# VisualightMicroDIY_035_gnd.net
KiCad netlist of a schematic drawn in EAGLE
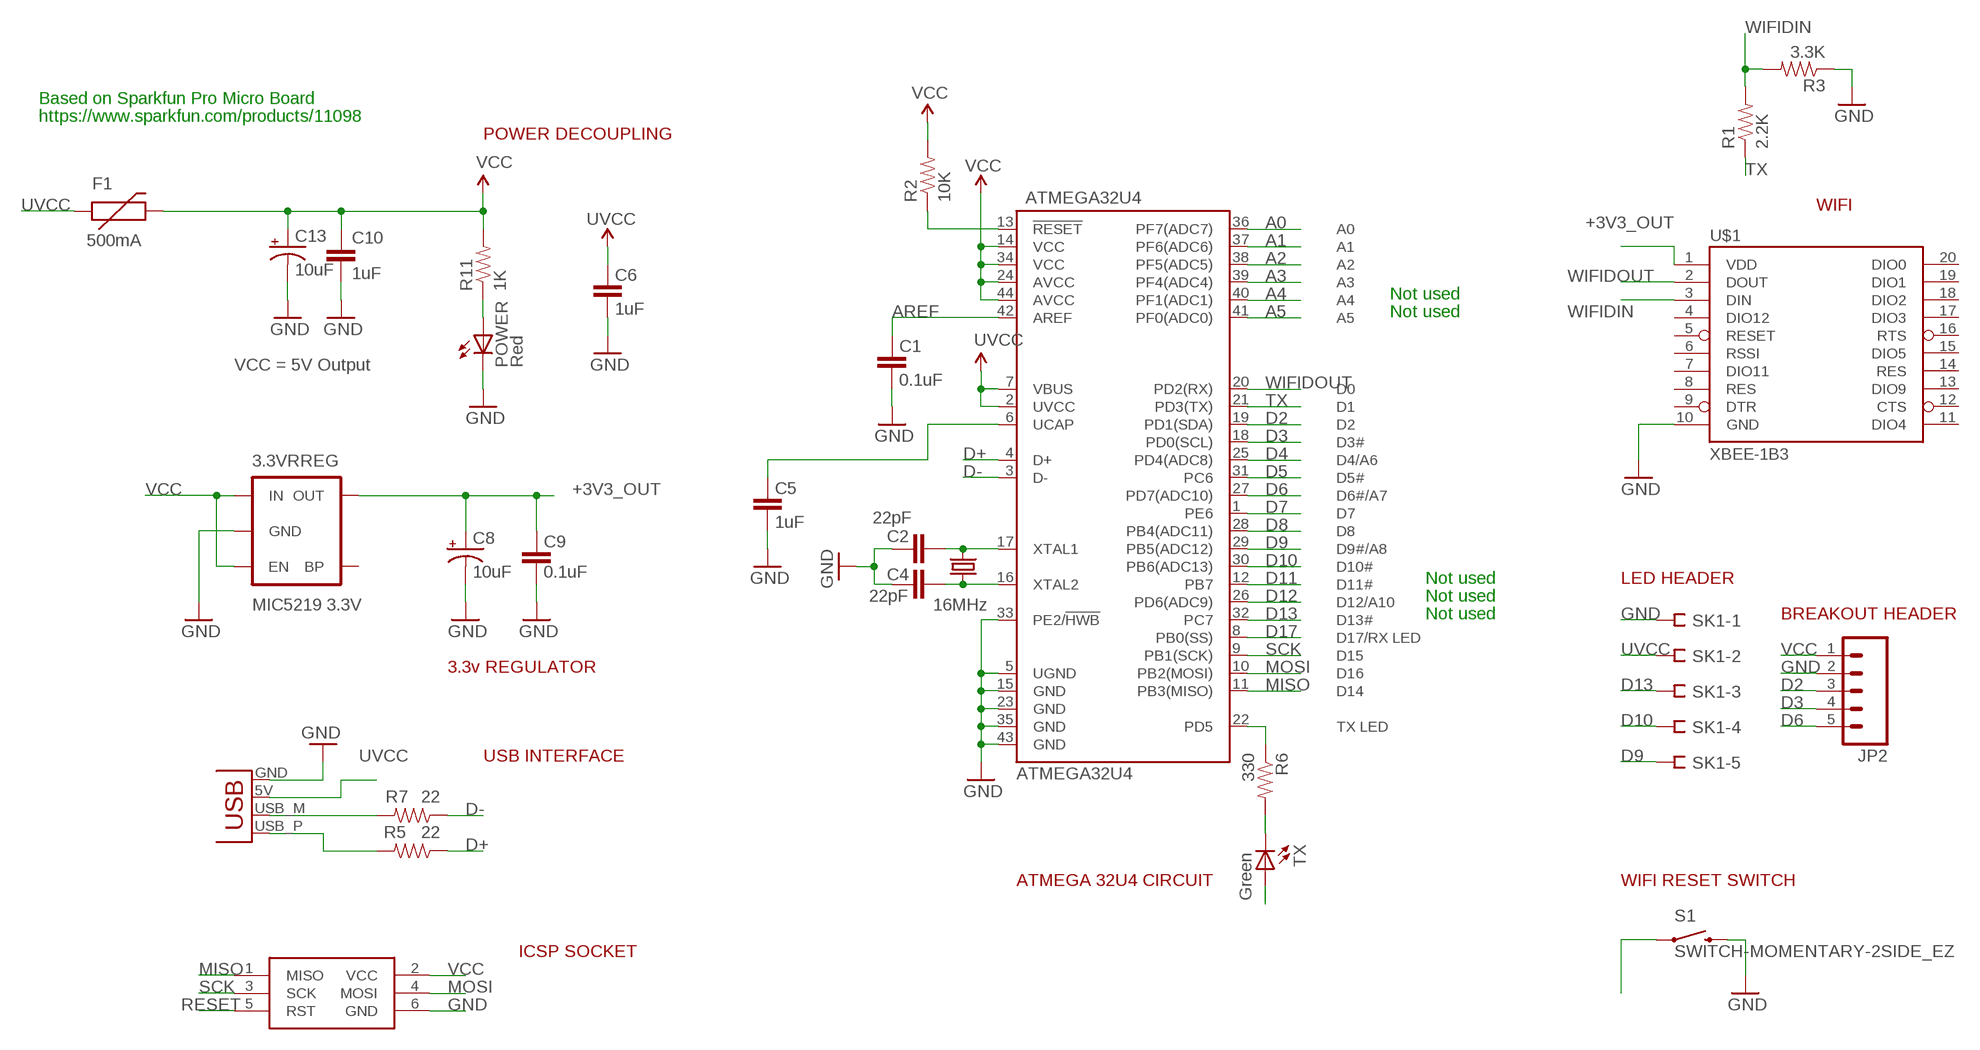
[diagram p0: schematic, sheet 1]

(export (version "E")
  (design (tool "Eeschema 10.0.6"))
  (components
    (comp (ref "3.3VRREG")
      (value "MIC5219 3.3V")
      (footprint "eagle-import:SOT23-5")
      (libsource (lib "eagle-import") (part "V_REG_MIC52193.3V"))
    )
    (comp (ref "ATMEGA32U4")
      (value "ATMEGA32U4")
      (footprint "eagle-import:SPARKFUN-DIGITALIC_TQFP44")
      (libsource (lib "eagle-import") (part "ATMEGA32U4TQFP"))
    )
    (comp (ref "C1")
      (value "0.1uF")
      (footprint "eagle-import:0402-CAP")
      (libsource (lib "eagle-import") (part "CAP0402-CAP"))
    )
    (comp (ref "C2")
      (value "22pF")
      (footprint "eagle-import:0402-CAP")
      (libsource (lib "eagle-import") (part "CAP0402-CAP"))
    )
    (comp (ref "C4")
      (value "22pF")
      (footprint "eagle-import:0402-CAP")
      (libsource (lib "eagle-import") (part "CAP0402-CAP"))
    )
    (comp (ref "C5")
      (value "1uF")
      (footprint "eagle-import:0402-CAP")
      (libsource (lib "eagle-import") (part "CAP0402-CAP"))
    )
    (comp (ref "C6")
      (value "1uF")
      (footprint "eagle-import:0402-CAP")
      (libsource (lib "eagle-import") (part "CAP0402-CAP"))
    )
    (comp (ref "C8")
      (value "10uF")
      (footprint "eagle-import:EIA3216")
      (libsource (lib "eagle-import") (part "CAP_POL1206"))
    )
    (comp (ref "C9")
      (value "0.1uF")
      (footprint "eagle-import:0402-CAP")
      (libsource (lib "eagle-import") (part "CAP0402-CAP"))
    )
    (comp (ref "C10")
      (value "1uF")
      (footprint "eagle-import:0402-CAP")
      (libsource (lib "eagle-import") (part "CAP0402-CAP"))
    )
    (comp (ref "C13")
      (value "10uF")
      (footprint "eagle-import:EIA3216")
      (libsource (lib "eagle-import") (part "CAP_POL1206"))
    )
    (comp (ref "F1")
      (value "500mA")
      (footprint "eagle-import:PTC-1206")
      (libsource (lib "eagle-import") (part "PTCSMD"))
    )
    (comp (ref "ISP1")
      (value "AVRISP-6")
      (footprint "eagle-import:AVRISP")
      (libsource (lib "eagle-import") (part "AVRISP-6"))
    )
    (comp (ref "JP2")
      (value "M05PTH")
      (footprint "eagle-import:1X05")
      (libsource (lib "eagle-import") (part "M05PTH"))
    )
    (comp (ref "POWER")
      (value "Red")
      (footprint "eagle-import:LED-0603")
      (libsource (lib "eagle-import") (part "LED0603"))
    )
    (comp (ref "R1")
      (value "2.2K")
      (footprint "eagle-import:0402-RES")
      (libsource (lib "eagle-import") (part "RESISTOR0402-RES"))
    )
    (comp (ref "R2")
      (value "10K")
      (footprint "eagle-import:0402-RES")
      (libsource (lib "eagle-import") (part "RESISTOR0402-RES"))
    )
    (comp (ref "R3")
      (value "3.3K")
      (footprint "eagle-import:0402-RES")
      (libsource (lib "eagle-import") (part "RESISTOR0402-RES"))
    )
    (comp (ref "R5")
      (value "22")
      (footprint "eagle-import:0402-RES")
      (libsource (lib "eagle-import") (part "RESISTOR0402-RES"))
    )
    (comp (ref "R6")
      (value "330")
      (footprint "eagle-import:0402-RES")
      (libsource (lib "eagle-import") (part "RESISTOR0402-RES"))
    )
    (comp (ref "R7")
      (value "22")
      (footprint "eagle-import:0402-RES")
      (libsource (lib "eagle-import") (part "RESISTOR0402-RES"))
    )
    (comp (ref "R11")
      (value "1K")
      (footprint "eagle-import:0402-RES")
      (libsource (lib "eagle-import") (part "RESISTOR0402-RES"))
    )
    (comp (ref "S1")
      (value "SWITCH-MOMENTARY-2SIDE_EZ")
      (footprint "eagle-import:TACTILE-PTH-SIDEEZ")
      (libsource (lib "eagle-import") (part "SWITCH-MOMENTARY-2SIDE_EZ"))
    )
    (comp (ref "SK1")
      (value "DF3-05S")
      (footprint "eagle-import:DF3S-05")
      (libsource (lib "eagle-import") (part "DF3-05S"))
    )
    (comp (ref "TX")
      (value "Green")
      (footprint "eagle-import:LED-0603")
      (libsource (lib "eagle-import") (part "LED0603"))
    )
    (comp (ref "U$1")
      (value "XBEE-1B3")
      (footprint "eagle-import:XBEE-SMD")
      (libsource (lib "eagle-import") (part "XBEE-1B3"))
    )
    (comp (ref "X2")
      (value "USBPCB")
      (footprint "eagle-import:USB-A-PCB")
      (libsource (lib "eagle-import") (part "USBPCB"))
    )
    (comp (ref "Y1")
      (value "16MHz")
      (footprint "eagle-import:CRYSTAL-SMD-5X3")
      (libsource (lib "eagle-import") (part "CRYSTAL5X3"))
    )
  )
  (nets
    (net (code "1") (name "/+3V3_OUT") (class "Default")
      (node (ref "3.3VRREG") (pin "5") (pinfunction "OUT_5") (pintype "passive"))
      (node (ref "C8") (pin "A") (pinfunction "+_A") (pintype "passive"))
      (node (ref "C9") (pin "2") (pinfunction "2_2") (pintype "passive"))
      (node (ref "U$1") (pin "1") (pinfunction "VDD_1") (pintype "power_in"))
    )
    (net (code "2") (name "/A0") (class "Default")
      (node (ref "ATMEGA32U4") (pin "36") (pinfunction "PF7(ADC7)_36") (pintype "bidirectional"))
    )
    (net (code "3") (name "/A1") (class "Default")
      (node (ref "ATMEGA32U4") (pin "37") (pinfunction "PF6(ADC6)_37") (pintype "bidirectional"))
    )
    (net (code "4") (name "/A2") (class "Default")
      (node (ref "ATMEGA32U4") (pin "38") (pinfunction "PF5(ADC5)_38") (pintype "bidirectional"))
    )
    (net (code "5") (name "/A3") (class "Default")
      (node (ref "ATMEGA32U4") (pin "39") (pinfunction "PF4(ADC4)_39") (pintype "bidirectional"))
    )
    (net (code "6") (name "/A4") (class "Default")
      (node (ref "ATMEGA32U4") (pin "40") (pinfunction "PF1(ADC1)_40") (pintype "bidirectional"))
    )
    (net (code "7") (name "/A5") (class "Default")
      (node (ref "ATMEGA32U4") (pin "41") (pinfunction "PF0(ADC0)_41") (pintype "bidirectional"))
    )
    (net (code "8") (name "/AREF") (class "Default")
      (node (ref "ATMEGA32U4") (pin "42") (pinfunction "AREF_42") (pintype "bidirectional"))
      (node (ref "C1") (pin "2") (pinfunction "2_2") (pintype "passive"))
    )
    (net (code "9") (name "/D+") (class "Default")
      (node (ref "ATMEGA32U4") (pin "4") (pinfunction "D+_4") (pintype "bidirectional"))
      (node (ref "R5") (pin "1") (pinfunction "1_1") (pintype "passive"))
    )
    (net (code "10") (name "/D-") (class "Default")
      (node (ref "ATMEGA32U4") (pin "3") (pinfunction "D-_3") (pintype "bidirectional"))
      (node (ref "R7") (pin "1") (pinfunction "1_1") (pintype "passive"))
    )
    (net (code "11") (name "/D2") (class "Default")
      (node (ref "ATMEGA32U4") (pin "19") (pinfunction "PD1(SDA)_19") (pintype "bidirectional"))
      (node (ref "JP2") (pin "3") (pinfunction "3_3") (pintype "passive"))
    )
    (net (code "12") (name "/D3") (class "Default")
      (node (ref "ATMEGA32U4") (pin "18") (pinfunction "PD0(SCL)_18") (pintype "bidirectional"))
      (node (ref "JP2") (pin "4") (pinfunction "4_4") (pintype "passive"))
    )
    (net (code "13") (name "/D4") (class "Default")
      (node (ref "ATMEGA32U4") (pin "25") (pinfunction "PD4(ADC8)_25") (pintype "bidirectional"))
    )
    (net (code "14") (name "/D5") (class "Default")
      (node (ref "ATMEGA32U4") (pin "31") (pinfunction "PC6_31") (pintype "bidirectional"))
    )
    (net (code "15") (name "/D6") (class "Default")
      (node (ref "ATMEGA32U4") (pin "27") (pinfunction "PD7(ADC10)_27") (pintype "bidirectional"))
      (node (ref "JP2") (pin "5") (pinfunction "5_5") (pintype "passive"))
    )
    (net (code "16") (name "/D7") (class "Default")
      (node (ref "ATMEGA32U4") (pin "1") (pinfunction "PE6_1") (pintype "bidirectional"))
      (node (ref "S1") (pin "1") (pinfunction "1_1") (pintype "passive"))
    )
    (net (code "17") (name "/D8") (class "Default")
      (node (ref "ATMEGA32U4") (pin "28") (pinfunction "PB4(ADC11)_28") (pintype "bidirectional"))
    )
    (net (code "18") (name "/D9") (class "Default")
      (node (ref "ATMEGA32U4") (pin "29") (pinfunction "PB5(ADC12)_29") (pintype "bidirectional"))
      (node (ref "SK1") (pin "5") (pinfunction "S_5") (pintype "passive"))
    )
    (net (code "19") (name "/D10") (class "Default")
      (node (ref "ATMEGA32U4") (pin "30") (pinfunction "PB6(ADC13)_30") (pintype "bidirectional"))
      (node (ref "SK1") (pin "4") (pinfunction "S_4") (pintype "passive"))
    )
    (net (code "20") (name "/D11") (class "Default")
      (node (ref "ATMEGA32U4") (pin "12") (pinfunction "PB7_12") (pintype "bidirectional"))
    )
    (net (code "21") (name "/D12") (class "Default")
      (node (ref "ATMEGA32U4") (pin "26") (pinfunction "PD6(ADC9)_26") (pintype "bidirectional"))
    )
    (net (code "22") (name "/D13") (class "Default")
      (node (ref "ATMEGA32U4") (pin "32") (pinfunction "PC7_32") (pintype "bidirectional"))
      (node (ref "SK1") (pin "3") (pinfunction "S_3") (pintype "passive"))
    )
    (net (code "23") (name "/D17") (class "Default")
      (node (ref "ATMEGA32U4") (pin "8") (pinfunction "PB0(SS)_8") (pintype "bidirectional"))
    )
    (net (code "24") (name "/MISO") (class "Default")
      (node (ref "ATMEGA32U4") (pin "11") (pinfunction "PB3(MISO)_11") (pintype "bidirectional"))
      (node (ref "ISP1") (pin "1") (pinfunction "MISO_1") (pintype "input"))
    )
    (net (code "25") (name "/MOSI") (class "Default")
      (node (ref "ATMEGA32U4") (pin "10") (pinfunction "PB2(MOSI)_10") (pintype "bidirectional"))
      (node (ref "ISP1") (pin "4") (pinfunction "MOSI_4") (pintype "output"))
    )
    (net (code "26") (name "/RESET") (class "Default")
      (node (ref "ATMEGA32U4") (pin "13") (pinfunction "~{RESET}_13") (pintype "bidirectional"))
      (node (ref "ISP1") (pin "5") (pinfunction "RST_5") (pintype "output"))
      (node (ref "R2") (pin "1") (pinfunction "1_1") (pintype "passive"))
    )
    (net (code "27") (name "/SCK") (class "Default")
      (node (ref "ATMEGA32U4") (pin "9") (pinfunction "PB1(SCK)_9") (pintype "bidirectional"))
      (node (ref "ISP1") (pin "3") (pinfunction "SCK_3") (pintype "output"))
    )
    (net (code "28") (name "/TX") (class "Default")
      (node (ref "ATMEGA32U4") (pin "21") (pinfunction "PD3(TX)_21") (pintype "bidirectional"))
      (node (ref "R1") (pin "1") (pinfunction "1_1") (pintype "passive"))
    )
    (net (code "29") (name "/WIFIDIN") (class "Default")
      (node (ref "R1") (pin "2") (pinfunction "2_2") (pintype "passive"))
      (node (ref "R3") (pin "2") (pinfunction "2_2") (pintype "passive"))
      (node (ref "U$1") (pin "3") (pinfunction "DIN_3") (pintype "input"))
    )
    (net (code "30") (name "/WIFIDOUT") (class "Default")
      (node (ref "ATMEGA32U4") (pin "20") (pinfunction "PD2(RX)_20") (pintype "bidirectional"))
      (node (ref "U$1") (pin "2") (pinfunction "DOUT_2") (pintype "output"))
    )
    (net (code "31") (name "GND") (class "Default")
      (node (ref "3.3VRREG") (pin "2") (pinfunction "GND_2") (pintype "input"))
      (node (ref "ATMEGA32U4") (pin "15") (pinfunction "GND_15") (pintype "bidirectional"))
      (node (ref "ATMEGA32U4") (pin "23") (pinfunction "GND_23") (pintype "bidirectional"))
      (node (ref "ATMEGA32U4") (pin "33") (pinfunction "PE2/~{HWB}_33") (pintype "bidirectional"))
      (node (ref "ATMEGA32U4") (pin "35") (pinfunction "GND_35") (pintype "bidirectional"))
      (node (ref "ATMEGA32U4") (pin "43") (pinfunction "GND_43") (pintype "bidirectional"))
      (node (ref "ATMEGA32U4") (pin "5") (pinfunction "UGND_5") (pintype "bidirectional"))
      (node (ref "C1") (pin "1") (pinfunction "1_1") (pintype "passive"))
      (node (ref "C10") (pin "2") (pinfunction "2_2") (pintype "passive"))
      (node (ref "C13") (pin "C") (pinfunction "-_C") (pintype "passive"))
      (node (ref "C2") (pin "2") (pinfunction "2_2") (pintype "passive"))
      (node (ref "C4") (pin "2") (pinfunction "2_2") (pintype "passive"))
      (node (ref "C5") (pin "1") (pinfunction "1_1") (pintype "passive"))
      (node (ref "C6") (pin "1") (pinfunction "1_1") (pintype "passive"))
      (node (ref "C8") (pin "C") (pinfunction "-_C") (pintype "passive"))
      (node (ref "C9") (pin "1") (pinfunction "1_1") (pintype "passive"))
      (node (ref "ISP1") (pin "6") (pinfunction "GND_6") (pintype "power_in"))
      (node (ref "JP2") (pin "2") (pinfunction "2_2") (pintype "passive"))
      (node (ref "POWER") (pin "C") (pinfunction "C_C") (pintype "passive"))
      (node (ref "R3") (pin "1") (pinfunction "1_1") (pintype "passive"))
      (node (ref "S1") (pin "2") (pinfunction "2_2") (pintype "passive"))
      (node (ref "SK1") (pin "1") (pinfunction "S_1") (pintype "passive"))
      (node (ref "U$1") (pin "10") (pinfunction "GND_10") (pintype "power_in"))
      (node (ref "X2") (pin "GND") (pinfunction "GND_GND") (pintype "bidirectional"))
    )
    (net (code "32") (name "Net-(ATMEGA32U4-PD5)") (class "Default")
      (node (ref "ATMEGA32U4") (pin "22") (pinfunction "PD5_22") (pintype "bidirectional"))
      (node (ref "R6") (pin "1") (pinfunction "1_1") (pintype "passive"))
    )
    (net (code "33") (name "Net-(ATMEGA32U4-UCAP)") (class "Default")
      (node (ref "ATMEGA32U4") (pin "6") (pinfunction "UCAP_6") (pintype "bidirectional"))
      (node (ref "C5") (pin "2") (pinfunction "2_2") (pintype "passive"))
    )
    (net (code "34") (name "Net-(ATMEGA32U4-XTAL1)") (class "Default")
      (node (ref "ATMEGA32U4") (pin "17") (pinfunction "XTAL1_17") (pintype "bidirectional"))
      (node (ref "C2") (pin "1") (pinfunction "1_1") (pintype "passive"))
      (node (ref "Y1") (pin "3") (pinfunction "2_3") (pintype "passive"))
    )
    (net (code "35") (name "Net-(ATMEGA32U4-XTAL2)") (class "Default")
      (node (ref "ATMEGA32U4") (pin "16") (pinfunction "XTAL2_16") (pintype "bidirectional"))
      (node (ref "C4") (pin "1") (pinfunction "1_1") (pintype "passive"))
      (node (ref "Y1") (pin "1") (pinfunction "1_1") (pintype "passive"))
    )
    (net (code "36") (name "Net-(POWER-PadA)") (class "Default")
      (node (ref "POWER") (pin "A") (pinfunction "A_A") (pintype "passive"))
      (node (ref "R11") (pin "1") (pinfunction "1_1") (pintype "passive"))
    )
    (net (code "37") (name "Net-(R6-Pad2)") (class "Default")
      (node (ref "R6") (pin "2") (pinfunction "2_2") (pintype "passive"))
      (node (ref "TX") (pin "C") (pinfunction "C_C") (pintype "passive"))
    )
    (net (code "38") (name "Net-(X2-D+)") (class "Default")
      (node (ref "R5") (pin "2") (pinfunction "2_2") (pintype "passive"))
      (node (ref "X2") (pin "USB_P") (pinfunction "D+_USB_P") (pintype "bidirectional"))
    )
    (net (code "39") (name "Net-(X2-D-)") (class "Default")
      (node (ref "R7") (pin "2") (pinfunction "2_2") (pintype "passive"))
      (node (ref "X2") (pin "USB_M") (pinfunction "D-_USB_M") (pintype "bidirectional"))
    )
    (net (code "40") (name "UVCC") (class "Default")
      (node (ref "ATMEGA32U4") (pin "2") (pinfunction "UVCC_2") (pintype "bidirectional"))
      (node (ref "ATMEGA32U4") (pin "7") (pinfunction "VBUS_7") (pintype "bidirectional"))
      (node (ref "C6") (pin "2") (pinfunction "2_2") (pintype "passive"))
      (node (ref "F1") (pin "1") (pinfunction "1_1") (pintype "bidirectional"))
      (node (ref "SK1") (pin "2") (pinfunction "S_2") (pintype "passive"))
      (node (ref "X2") (pin "5V") (pinfunction "VBUS_5V") (pintype "bidirectional"))
    )
    (net (code "41") (name "VCC") (class "Default")
      (node (ref "3.3VRREG") (pin "1") (pinfunction "IN_1") (pintype "input"))
      (node (ref "3.3VRREG") (pin "3") (pinfunction "EN_3") (pintype "input"))
      (node (ref "ATMEGA32U4") (pin "14") (pinfunction "VCC_14") (pintype "bidirectional"))
      (node (ref "ATMEGA32U4") (pin "24") (pinfunction "AVCC_24") (pintype "bidirectional"))
      (node (ref "ATMEGA32U4") (pin "34") (pinfunction "VCC_34") (pintype "bidirectional"))
      (node (ref "ATMEGA32U4") (pin "44") (pinfunction "AVCC_44") (pintype "bidirectional"))
      (node (ref "C10") (pin "1") (pinfunction "1_1") (pintype "passive"))
      (node (ref "C13") (pin "A") (pinfunction "+_A") (pintype "passive"))
      (node (ref "F1") (pin "2") (pinfunction "2_2") (pintype "bidirectional"))
      (node (ref "ISP1") (pin "2") (pinfunction "VCC_2") (pintype "power_in"))
      (node (ref "JP2") (pin "1") (pinfunction "1_1") (pintype "passive"))
      (node (ref "R11") (pin "2") (pinfunction "2_2") (pintype "passive"))
      (node (ref "R2") (pin "2") (pinfunction "2_2") (pintype "passive"))
      (node (ref "TX") (pin "A") (pinfunction "A_A") (pintype "passive"))
    )
    (net (code "42") (name "unconnected-(3.3VRREG-BP-Pad4)") (class "Default")
      (node (ref "3.3VRREG") (pin "4") (pinfunction "BP_4") (pintype "input"))
    )
    (net (code "43") (name "unconnected-(U$1-CTS-Pad12)") (class "Default")
      (node (ref "U$1") (pin "12") (pinfunction "CTS_12") (pintype "output"))
    )
    (net (code "44") (name "unconnected-(U$1-DIO0-Pad20)") (class "Default")
      (node (ref "U$1") (pin "20") (pinfunction "DIO0_20") (pintype "bidirectional"))
    )
    (net (code "45") (name "unconnected-(U$1-DIO1-Pad19)") (class "Default")
      (node (ref "U$1") (pin "19") (pinfunction "DIO1_19") (pintype "bidirectional"))
    )
    (net (code "46") (name "unconnected-(U$1-DIO2-Pad18)") (class "Default")
      (node (ref "U$1") (pin "18") (pinfunction "DIO2_18") (pintype "bidirectional"))
    )
    (net (code "47") (name "unconnected-(U$1-DIO3-Pad17)") (class "Default")
      (node (ref "U$1") (pin "17") (pinfunction "DIO3_17") (pintype "bidirectional"))
    )
    (net (code "48") (name "unconnected-(U$1-DIO4-Pad11)") (class "Default")
      (node (ref "U$1") (pin "11") (pinfunction "DIO4_11") (pintype "bidirectional"))
    )
    (net (code "49") (name "unconnected-(U$1-DIO5-Pad15)") (class "Default")
      (node (ref "U$1") (pin "15") (pinfunction "DIO5_15") (pintype "bidirectional"))
    )
    (net (code "50") (name "unconnected-(U$1-DIO9-Pad13)") (class "Default")
      (node (ref "U$1") (pin "13") (pinfunction "DIO9_13") (pintype "bidirectional"))
    )
    (net (code "51") (name "unconnected-(U$1-DIO11-Pad7)") (class "Default")
      (node (ref "U$1") (pin "7") (pinfunction "DIO11_7") (pintype "bidirectional"))
    )
    (net (code "52") (name "unconnected-(U$1-DIO12-Pad4)") (class "Default")
      (node (ref "U$1") (pin "4") (pinfunction "DIO12_4") (pintype "bidirectional"))
    )
    (net (code "53") (name "unconnected-(U$1-DTR-Pad9)") (class "Default")
      (node (ref "U$1") (pin "9") (pinfunction "DTR_9") (pintype "bidirectional"))
    )
    (net (code "54") (name "unconnected-(U$1-RES-Pad8)") (class "Default")
      (node (ref "U$1") (pin "8") (pinfunction "RES_8") (pintype "bidirectional"))
    )
    (net (code "55") (name "unconnected-(U$1-RES-Pad14)") (class "Default")
      (node (ref "U$1") (pin "14") (pinfunction "RES_14") (pintype "bidirectional"))
    )
    (net (code "56") (name "unconnected-(U$1-RESET-Pad5)") (class "Default")
      (node (ref "U$1") (pin "5") (pinfunction "RESET_5") (pintype "input"))
    )
    (net (code "57") (name "unconnected-(U$1-RSSI-Pad6)") (class "Default")
      (node (ref "U$1") (pin "6") (pinfunction "RSSI_6") (pintype "bidirectional"))
    )
    (net (code "58") (name "unconnected-(U$1-RTS-Pad16)") (class "Default")
      (node (ref "U$1") (pin "16") (pinfunction "RTS_16") (pintype "input"))
    )
  )
)
